# BMSv3.net
KiCad netlist of a schematic drawn in EAGLE
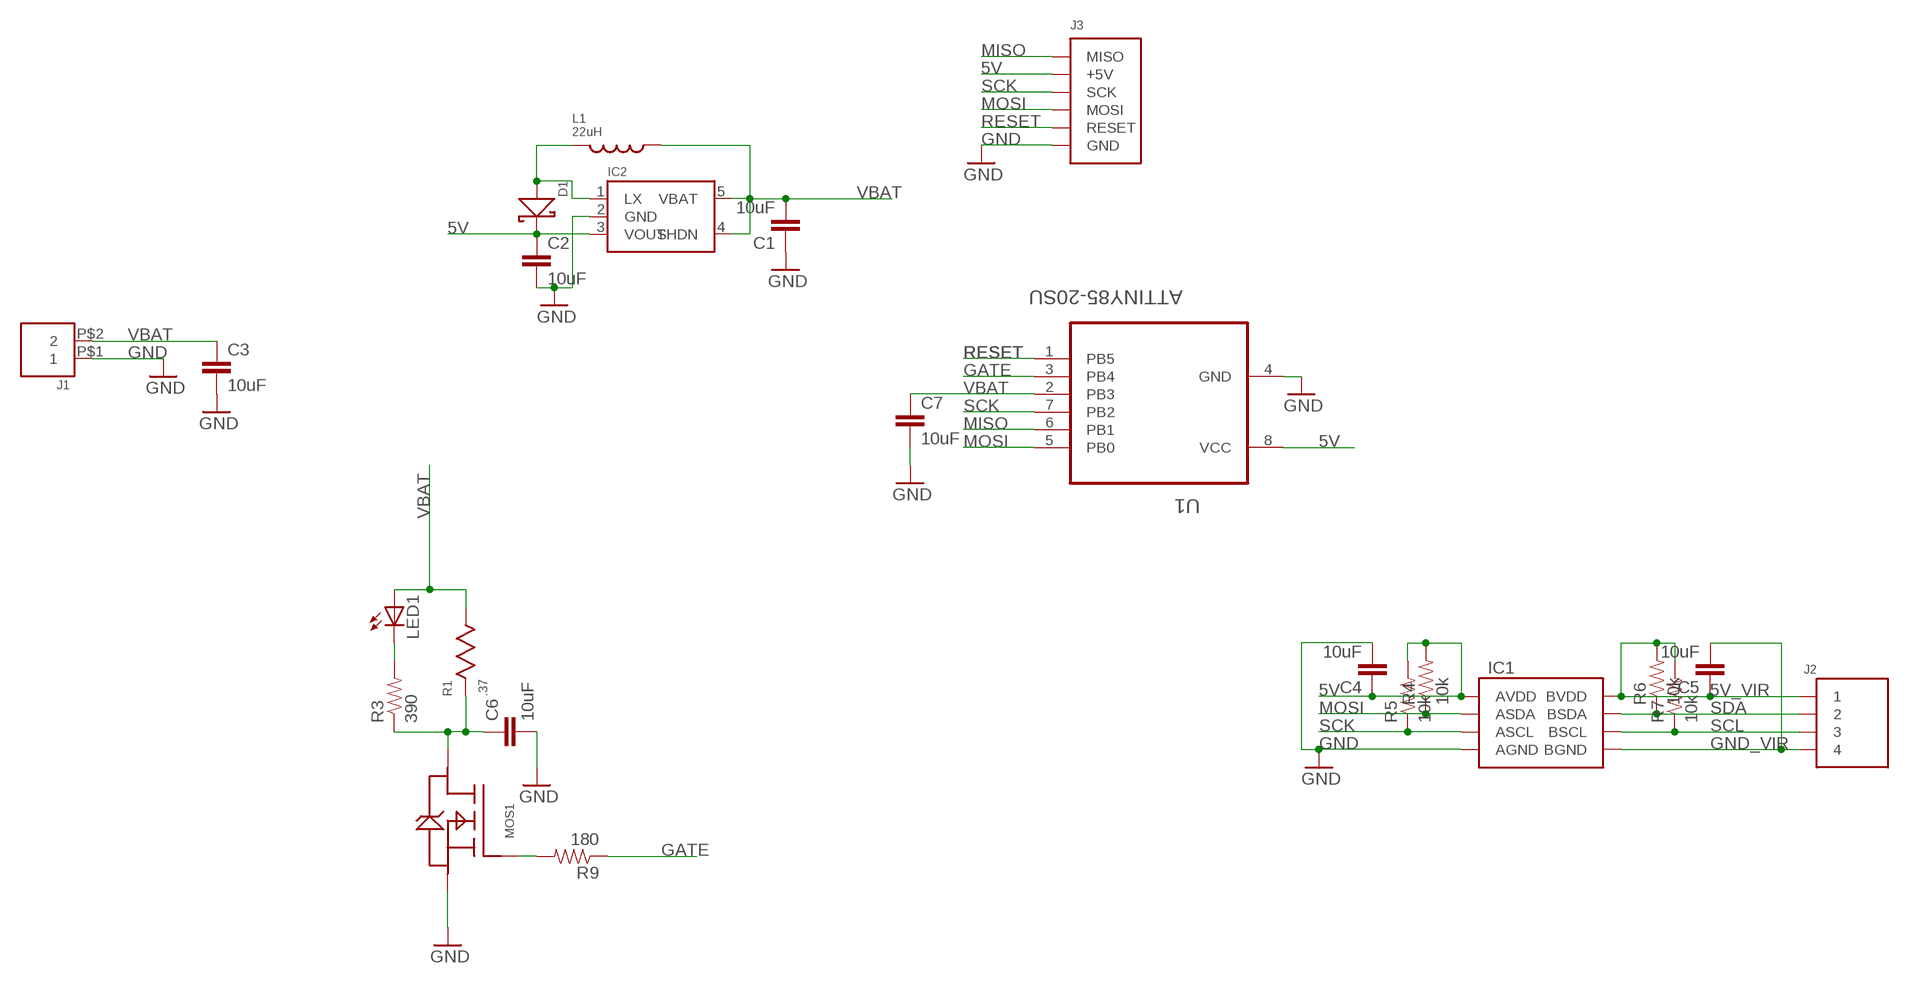
[diagram p0: schematic, sheet 1]

(export (version "E")
  (design (tool "Eeschema 10.0.6"))
  (components
    (comp (ref "C1")
      (value "10uF")
      (footprint "eagle-import:0805-CAP")
      (libsource (lib "eagle-import") (part "10UF10V10%(0805)"))
    )
    (comp (ref "C2")
      (value "10uF")
      (footprint "eagle-import:0805-CAP")
      (libsource (lib "eagle-import") (part "10UF10V10%(0805)"))
    )
    (comp (ref "C3")
      (value "10uF")
      (footprint "eagle-import:0805-CAP")
      (libsource (lib "eagle-import") (part "10UF10V10%(0805)"))
    )
    (comp (ref "C4")
      (value "10uF")
      (footprint "eagle-import:0805-CAP")
      (libsource (lib "eagle-import") (part "10UF10V10%(0805)"))
    )
    (comp (ref "C5")
      (value "10uF")
      (footprint "eagle-import:0805-CAP")
      (libsource (lib "eagle-import") (part "10UF10V10%(0805)"))
    )
    (comp (ref "C6")
      (value "10uF")
      (footprint "eagle-import:0805-CAP")
      (libsource (lib "eagle-import") (part "10UF10V10%(0805)"))
    )
    (comp (ref "C7")
      (value "10uF")
      (footprint "eagle-import:0805-CAP")
      (libsource (lib "eagle-import") (part "10UF10V10%(0805)"))
    )
    (comp (ref "D1")
      (value "DIODE_SCHOTTKYSOD-123")
      (footprint "eagle-import:SOD-123")
      (libsource (lib "eagle-import") (part "DIODE_SCHOTTKYSOD-123"))
    )
    (comp (ref "IC1")
      (value "SI8600_DUALCHANNELISO")
      (footprint "eagle-import:SOIC-8")
      (libsource (lib "eagle-import") (part "SI8600_DUALCHANNELISO"))
    )
    (comp (ref "IC2")
      (value "SP6641")
      (footprint "eagle-import:SOT-23")
      (libsource (lib "eagle-import") (part "SP6641"))
    )
    (comp (ref "J1")
      (value "CONNECTOR_2PIN")
      (footprint "eagle-import:2PIN_.1'")
      (libsource (lib "eagle-import") (part "CONNECTOR_2PIN"))
    )
    (comp (ref "J2")
      (value "CONNECTOR_4PIN")
      (footprint "eagle-import:4PIN_.1'")
      (libsource (lib "eagle-import") (part "CONNECTOR_4PIN"))
    )
    (comp (ref "J3")
      (value "ISPHEADER")
      (footprint "eagle-import:2X3PIN_.1'")
      (libsource (lib "eagle-import") (part "ISPHEADER"))
    )
    (comp (ref "L1")
      (value "22uH")
      (footprint "eagle-import:6X6MM_IND")
      (libsource (lib "eagle-import") (part "CHIP_IND1"))
    )
    (comp (ref "LED1")
      (value "LEDCHIPLED_0805")
      (footprint "eagle-import:CHIPLED_0805")
      (libsource (lib "eagle-import") (part "LEDCHIPLED_0805"))
    )
    (comp (ref "MOS1")
      (value "MOS_N_LOGIC_PSMN7R0")
      (footprint "eagle-import:LFPAK")
      (libsource (lib "eagle-import") (part "MOS_N_LOGIC_PSMN7R0"))
    )
    (comp (ref "R1")
      (value ".37")
      (footprint "eagle-import:TO-220-2")
      (libsource (lib "eagle-import") (part "RES_THROUGH"))
    )
    (comp (ref "R3")
      (value "390")
      (footprint "eagle-import:0805")
      (libsource (lib "eagle-import") (part "0.3OHM-1/8W-1%(0805)"))
    )
    (comp (ref "R4")
      (value "10k")
      (footprint "eagle-import:0805")
      (libsource (lib "eagle-import") (part "0.3OHM-1/8W-1%(0805)"))
    )
    (comp (ref "R5")
      (value "10k")
      (footprint "eagle-import:0805")
      (libsource (lib "eagle-import") (part "0.3OHM-1/8W-1%(0805)"))
    )
    (comp (ref "R6")
      (value "10k")
      (footprint "eagle-import:0805")
      (libsource (lib "eagle-import") (part "0.3OHM-1/8W-1%(0805)"))
    )
    (comp (ref "R7")
      (value "10k")
      (footprint "eagle-import:0805")
      (libsource (lib "eagle-import") (part "0.3OHM-1/8W-1%(0805)"))
    )
    (comp (ref "R9")
      (value "180")
      (footprint "eagle-import:0805")
      (libsource (lib "eagle-import") (part "0.3OHM-1/8W-1%(0805)"))
    )
    (comp (ref "U1")
      (value "ATTINY85-20SU")
      (footprint "eagle-import:SOIC127P798X216-8N")
      (libsource (lib "eagle-import") (part "ATTINY85-20SU"))
    )
  )
  (nets
    (net (code "1") (name "/5V") (class "Default")
      (node (ref "C2") (pin "1") (pinfunction "1_1") (pintype "passive"))
      (node (ref "C4") (pin "1") (pinfunction "1_1") (pintype "passive"))
      (node (ref "D1") (pin "CATHODE") (pinfunction "CATHODE_CATHODE") (pintype "bidirectional"))
      (node (ref "IC1") (pin "P$1") (pinfunction "AVDD_P$1") (pintype "bidirectional"))
      (node (ref "IC2") (pin "3") (pinfunction "VOUT_3") (pintype "bidirectional"))
      (node (ref "J3") (pin "P$2") (pinfunction "+5V_P$2") (pintype "bidirectional"))
      (node (ref "R4") (pin "2") (pinfunction "2_2") (pintype "passive"))
      (node (ref "R5") (pin "2") (pinfunction "2_2") (pintype "passive"))
      (node (ref "U1") (pin "8") (pinfunction "VCC_8") (pintype "power_in"))
    )
    (net (code "2") (name "/5V_VIR") (class "Default")
      (node (ref "C5") (pin "1") (pinfunction "1_1") (pintype "passive"))
      (node (ref "IC1") (pin "P$8") (pinfunction "BVDD_P$8") (pintype "bidirectional"))
      (node (ref "J2") (pin "P$1") (pinfunction "1_P$1") (pintype "bidirectional"))
      (node (ref "R6") (pin "2") (pinfunction "2_2") (pintype "passive"))
      (node (ref "R7") (pin "2") (pinfunction "2_2") (pintype "passive"))
    )
    (net (code "3") (name "/GATE") (class "Default")
      (node (ref "R9") (pin "1") (pinfunction "1_1") (pintype "passive"))
      (node (ref "U1") (pin "3") (pinfunction "PB4_3") (pintype "bidirectional"))
    )
    (net (code "4") (name "/GND_VIR") (class "Default")
      (node (ref "C5") (pin "2") (pinfunction "2_2") (pintype "passive"))
      (node (ref "IC1") (pin "P$5") (pinfunction "BGND_P$5") (pintype "bidirectional"))
      (node (ref "J2") (pin "P$4") (pinfunction "4_P$4") (pintype "bidirectional"))
    )
    (net (code "5") (name "/MISO") (class "Default")
      (node (ref "J3") (pin "P$1") (pinfunction "MISO_P$1") (pintype "bidirectional"))
      (node (ref "U1") (pin "6") (pinfunction "PB1_6") (pintype "bidirectional"))
    )
    (net (code "6") (name "/MOSI") (class "Default")
      (node (ref "IC1") (pin "P$2") (pinfunction "ASDA_P$2") (pintype "bidirectional"))
      (node (ref "J3") (pin "P$4") (pinfunction "MOSI_P$4") (pintype "bidirectional"))
      (node (ref "R4") (pin "1") (pinfunction "1_1") (pintype "passive"))
      (node (ref "U1") (pin "5") (pinfunction "PB0_5") (pintype "bidirectional"))
    )
    (net (code "7") (name "/RESET") (class "Default")
      (node (ref "J3") (pin "P$5") (pinfunction "RESET_P$5") (pintype "bidirectional"))
      (node (ref "U1") (pin "1") (pinfunction "PB5_1") (pintype "bidirectional"))
    )
    (net (code "8") (name "/SCK") (class "Default")
      (node (ref "IC1") (pin "P$3") (pinfunction "ASCL_P$3") (pintype "bidirectional"))
      (node (ref "J3") (pin "P$3") (pinfunction "SCK_P$3") (pintype "bidirectional"))
      (node (ref "R5") (pin "1") (pinfunction "1_1") (pintype "passive"))
      (node (ref "U1") (pin "7") (pinfunction "PB2_7") (pintype "bidirectional"))
    )
    (net (code "9") (name "/SCL") (class "Default")
      (node (ref "IC1") (pin "P$6") (pinfunction "BSCL_P$6") (pintype "bidirectional"))
      (node (ref "J2") (pin "P$3") (pinfunction "3_P$3") (pintype "bidirectional"))
      (node (ref "R7") (pin "1") (pinfunction "1_1") (pintype "passive"))
    )
    (net (code "10") (name "/SDA") (class "Default")
      (node (ref "IC1") (pin "P$7") (pinfunction "BSDA_P$7") (pintype "bidirectional"))
      (node (ref "J2") (pin "P$2") (pinfunction "2_P$2") (pintype "bidirectional"))
      (node (ref "R6") (pin "1") (pinfunction "1_1") (pintype "passive"))
    )
    (net (code "11") (name "/VBAT") (class "Default")
      (node (ref "C1") (pin "2") (pinfunction "2_2") (pintype "passive"))
      (node (ref "C3") (pin "1") (pinfunction "1_1") (pintype "passive"))
      (node (ref "C7") (pin "1") (pinfunction "1_1") (pintype "passive"))
      (node (ref "IC2") (pin "4") (pinfunction "SHDN_4") (pintype "bidirectional"))
      (node (ref "IC2") (pin "5") (pinfunction "VBAT_5") (pintype "bidirectional"))
      (node (ref "J1") (pin "P$2") (pinfunction "2_P$2") (pintype "bidirectional"))
      (node (ref "L1") (pin "P$2") (pinfunction "P$2_P$2") (pintype "bidirectional"))
      (node (ref "LED1") (pin "A") (pinfunction "A_A") (pintype "passive"))
      (node (ref "R1") (pin "P$2") (pinfunction "P$2_P$2") (pintype "bidirectional"))
      (node (ref "U1") (pin "2") (pinfunction "PB3_2") (pintype "bidirectional"))
    )
    (net (code "12") (name "GND") (class "Default")
      (node (ref "C1") (pin "1") (pinfunction "1_1") (pintype "passive"))
      (node (ref "C2") (pin "2") (pinfunction "2_2") (pintype "passive"))
      (node (ref "C3") (pin "2") (pinfunction "2_2") (pintype "passive"))
      (node (ref "C4") (pin "2") (pinfunction "2_2") (pintype "passive"))
      (node (ref "C6") (pin "2") (pinfunction "2_2") (pintype "passive"))
      (node (ref "C7") (pin "2") (pinfunction "2_2") (pintype "passive"))
      (node (ref "IC1") (pin "P$4") (pinfunction "AGND_P$4") (pintype "bidirectional"))
      (node (ref "IC2") (pin "2") (pinfunction "GND_2") (pintype "bidirectional"))
      (node (ref "J1") (pin "P$1") (pinfunction "1_P$1") (pintype "bidirectional"))
      (node (ref "J3") (pin "P$6") (pinfunction "GND_P$6") (pintype "bidirectional"))
      (node (ref "MOS1") (pin "P$1") (pinfunction "SOURCE_P$1") (pintype "bidirectional"))
      (node (ref "MOS1") (pin "P$2") (pinfunction "SOURCE_P$2") (pintype "bidirectional"))
      (node (ref "MOS1") (pin "P$3") (pinfunction "SOURCE_P$3") (pintype "bidirectional"))
      (node (ref "U1") (pin "4") (pinfunction "GND_4") (pintype "passive"))
    )
    (net (code "13") (name "Net-(IC2-LX)") (class "Default")
      (node (ref "D1") (pin "ANODE") (pinfunction "ANODE_ANODE") (pintype "bidirectional"))
      (node (ref "IC2") (pin "1") (pinfunction "LX_1") (pintype "bidirectional"))
      (node (ref "L1") (pin "P$1") (pinfunction "P$1_P$1") (pintype "bidirectional"))
    )
    (net (code "14") (name "Net-(LED1-PadC)") (class "Default")
      (node (ref "LED1") (pin "C") (pinfunction "C_C") (pintype "passive"))
      (node (ref "R3") (pin "2") (pinfunction "2_2") (pintype "passive"))
    )
    (net (code "15") (name "Net-(MOS1-DRAIN)") (class "Default")
      (node (ref "C6") (pin "1") (pinfunction "1_1") (pintype "passive"))
      (node (ref "MOS1") (pin "P$5") (pinfunction "DRAIN_P$5") (pintype "bidirectional"))
      (node (ref "R1") (pin "P$1") (pinfunction "P$1_P$1") (pintype "bidirectional"))
      (node (ref "R3") (pin "1") (pinfunction "1_1") (pintype "passive"))
    )
    (net (code "16") (name "Net-(MOS1-GATE)") (class "Default")
      (node (ref "MOS1") (pin "P$4") (pinfunction "GATE_P$4") (pintype "bidirectional"))
      (node (ref "R9") (pin "2") (pinfunction "2_2") (pintype "passive"))
    )
  )
)
